# cRamageddon.net
KiCad netlist of a schematic drawn in EasyEDA
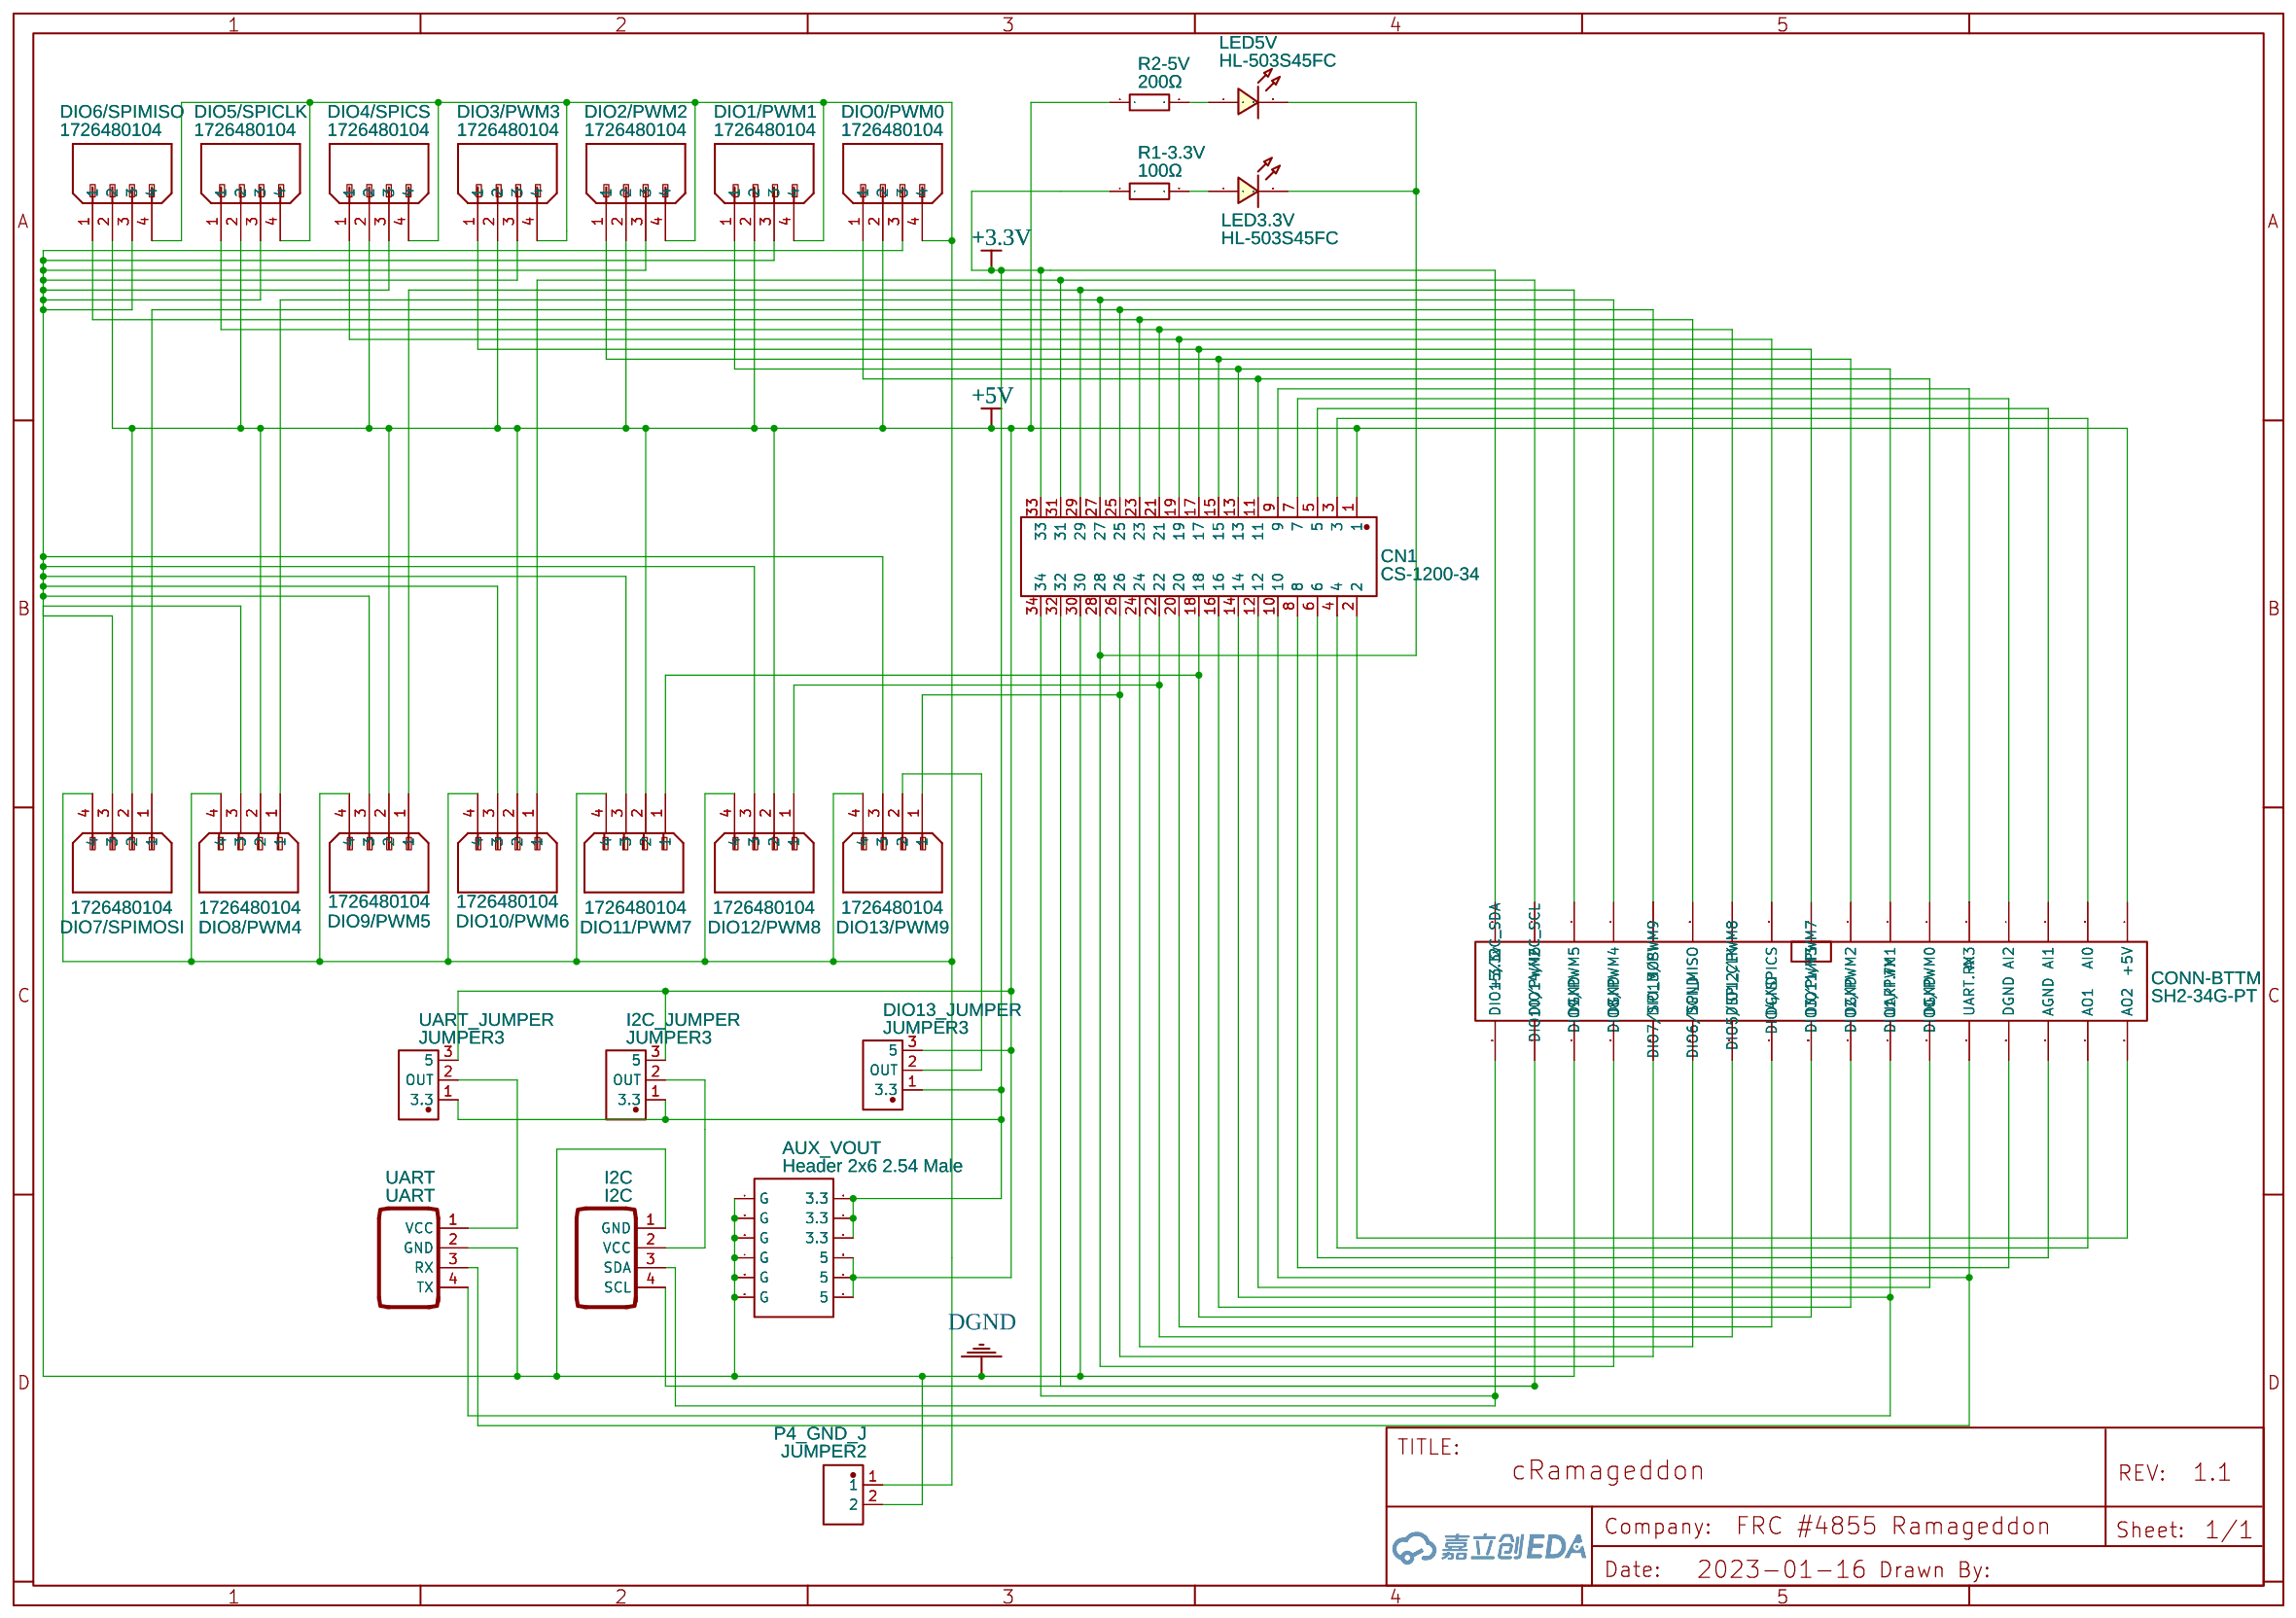
[diagram p0: schematic sheet]

(export (version "E")
  (design (tool "Eeschema 10.0.6"))
  (components
    (comp (ref "AUX_VOUT")
      (value "Header 2x6 2.54 Male")
      (fields (field (name "BOM_Supplier Part") "2X5/2.54"))
      (libsource (lib "") (part "Header 2x6 2.54 Male"))
    )
    (comp (ref "CN1")
      (value "CS-1200-34")
      (fields (field (name "BOM_Supplier Part") "C2886707"))
      (libsource (lib "") (part "CS-1200-34"))
    )
    (comp (ref "CONN-BTTM") (value "SH2-34G-PT") (libsource (lib "") (part "SH2-34G-PT")))
    (comp (ref "DIO0/PWM0") (value "1726480104") (libsource (lib "") (part "1726480104_1")))
    (comp (ref "DIO1/PWM1") (value "1726480104") (libsource (lib "") (part "1726480104_13")))
    (comp (ref "DIO2/PWM2") (value "1726480104") (libsource (lib "") (part "1726480104_7")))
    (comp (ref "DIO3/PWM3") (value "1726480104") (libsource (lib "") (part "1726480104_12")))
    (comp (ref "DIO4/SPICS") (value "1726480104") (libsource (lib "") (part "1726480104_4")))
    (comp (ref "DIO5/SPICLK") (value "1726480104") (libsource (lib "") (part "1726480104_8")))
    (comp (ref "DIO6/SPIMISO") (value "1726480104") (libsource (lib "") (part "1726480104_3")))
    (comp (ref "DIO7/SPIMOSI") (value "1726480104") (libsource (lib "") (part "1726480104")))
    (comp (ref "DIO8/PWM4") (value "1726480104") (libsource (lib "") (part "1726480104_11")))
    (comp (ref "DIO9/PWM5") (value "1726480104") (libsource (lib "") (part "1726480104_9")))
    (comp (ref "DIO10/PWM6") (value "1726480104") (libsource (lib "") (part "1726480104_6")))
    (comp (ref "DIO11/PWM7") (value "1726480104") (libsource (lib "") (part "1726480104_2")))
    (comp (ref "DIO12/PWM8") (value "1726480104") (libsource (lib "") (part "1726480104_10")))
    (comp (ref "DIO13/PWM9") (value "1726480104") (libsource (lib "") (part "1726480104_5")))
    (comp (ref "DIO13_JUMPER")
      (value "JUMPER3")
      (fields (field (name "BOM_Manufacturer Part") "Jumper3") (field (name "BOM_Supplier Part") "C2940050"))
      (libsource (lib "") (part "JUMPER3_1"))
    )
    (comp (ref "I2C")
      (value "I2C")
      (fields (field (name "BOM_Supplier Part") "Módulo para LCD"))
      (libsource (lib "") (part "I2C_1"))
    )
    (comp (ref "I2C_JUMPER")
      (value "JUMPER3")
      (fields (field (name "BOM_Manufacturer Part") "Jumper3") (field (name "BOM_Supplier Part") "C2940050"))
      (libsource (lib "") (part "JUMPER3_2"))
    )
    (comp (ref "LED3.3V")
      (value "HL-503S45FC")
      (fields (field (name "BOM_Supplier Part") "C568942"))
      (libsource (lib "") (part "HL-503S45FC"))
    )
    (comp (ref "LED5V")
      (value "HL-503S45FC")
      (fields (field (name "BOM_Supplier Part") "C568942"))
      (libsource (lib "") (part "HL-503S45FC_1"))
    )
    (comp (ref "P4_GND_J")
      (value "JUMPER2")
      (fields (field (name "BOM_Manufacturer Part") "Jumper2") (field (name "BOM_Supplier Part") "C2940092"))
      (libsource (lib "") (part "JUMPER2"))
    )
    (comp (ref "R1-3.3V")
      (value "100Ω")
      (fields
        (field (name "BOM_Manufacturer Part") "MFR0W4F1800A50")
        (field (name "BOM_Supplier Part") "C58665")
      )
      (libsource (lib "") (part "MFR0W4F1800A50_1"))
    )
    (comp (ref "R2-5V")
      (value "200Ω")
      (fields
        (field (name "BOM_Manufacturer Part") "MFR0W4F1800A50")
        (field (name "BOM_Supplier Part") "C58665")
      )
      (libsource (lib "") (part "MFR0W4F1800A50"))
    )
    (comp (ref "UART")
      (value "UART")
      (fields (field (name "BOM_Supplier Part") "Módulo para LCD"))
      (libsource (lib "") (part "I2C"))
    )
    (comp (ref "UART_JUMPER")
      (value "JUMPER3")
      (fields (field (name "BOM_Manufacturer Part") "Jumper3") (field (name "BOM_Supplier Part") "C2940050"))
      (libsource (lib "") (part "JUMPER3"))
    )
  )
  (nets
    (net (code "1") (name "+3.3V") (class "Default")
      (node (ref "AUX_VOUT") (pin "2") (pinfunction "3.3_2") (pintype "unspecified"))
      (node (ref "AUX_VOUT") (pin "4") (pinfunction "3.3_4") (pintype "unspecified"))
      (node (ref "AUX_VOUT") (pin "6") (pinfunction "3.3_6") (pintype "unspecified"))
      (node (ref "CN1") (pin "33") (pinfunction "33_33") (pintype "unspecified"))
      (node (ref "CONN-BTTM") (pin "33") (pinfunction "+3.3v_33") (pintype "unspecified"))
      (node (ref "DIO13_JUMPER") (pin "1") (pinfunction "3.3_1") (pintype "unspecified"))
      (node (ref "I2C_JUMPER") (pin "1") (pinfunction "3.3_1") (pintype "unspecified"))
      (node (ref "R1-3.3V") (pin "1") (pinfunction "1_1") (pintype "input"))
      (node (ref "UART_JUMPER") (pin "1") (pinfunction "3.3_1") (pintype "unspecified"))
    )
    (net (code "2") (name "+5V") (class "Default")
      (node (ref "AUX_VOUT") (pin "10") (pinfunction "5_10") (pintype "unspecified"))
      (node (ref "AUX_VOUT") (pin "12") (pinfunction "5_12") (pintype "unspecified"))
      (node (ref "AUX_VOUT") (pin "8") (pinfunction "5_8") (pintype "unspecified"))
      (node (ref "CN1") (pin "1") (pinfunction "1_1") (pintype "unspecified"))
      (node (ref "CONN-BTTM") (pin "1") (pinfunction "+5V_1") (pintype "unspecified"))
      (node (ref "DIO0/PWM0") (pin "2") (pinfunction "2_2") (pintype "bidirectional"))
      (node (ref "DIO1/PWM1") (pin "2") (pinfunction "2_2") (pintype "bidirectional"))
      (node (ref "DIO10/PWM6") (pin "2") (pinfunction "2_2") (pintype "bidirectional"))
      (node (ref "DIO11/PWM7") (pin "2") (pinfunction "2_2") (pintype "bidirectional"))
      (node (ref "DIO12/PWM8") (pin "2") (pinfunction "2_2") (pintype "bidirectional"))
      (node (ref "DIO13_JUMPER") (pin "3") (pinfunction "5_3") (pintype "unspecified"))
      (node (ref "DIO2/PWM2") (pin "2") (pinfunction "2_2") (pintype "bidirectional"))
      (node (ref "DIO3/PWM3") (pin "2") (pinfunction "2_2") (pintype "bidirectional"))
      (node (ref "DIO4/SPICS") (pin "2") (pinfunction "2_2") (pintype "bidirectional"))
      (node (ref "DIO5/SPICLK") (pin "2") (pinfunction "2_2") (pintype "bidirectional"))
      (node (ref "DIO6/SPIMISO") (pin "2") (pinfunction "2_2") (pintype "bidirectional"))
      (node (ref "DIO7/SPIMOSI") (pin "2") (pinfunction "2_2") (pintype "bidirectional"))
      (node (ref "DIO8/PWM4") (pin "2") (pinfunction "2_2") (pintype "bidirectional"))
      (node (ref "DIO9/PWM5") (pin "2") (pinfunction "2_2") (pintype "bidirectional"))
      (node (ref "I2C_JUMPER") (pin "3") (pinfunction "5_3") (pintype "unspecified"))
      (node (ref "R2-5V") (pin "1") (pinfunction "1_1") (pintype "input"))
      (node (ref "UART_JUMPER") (pin "3") (pinfunction "5_3") (pintype "unspecified"))
    )
    (net (code "3") (name "DGND") (class "Default")
      (node (ref "AUX_VOUT") (pin "1") (pinfunction "G_1") (pintype "unspecified"))
      (node (ref "AUX_VOUT") (pin "11") (pinfunction "G_11") (pintype "unspecified"))
      (node (ref "AUX_VOUT") (pin "3") (pinfunction "G_3") (pintype "unspecified"))
      (node (ref "AUX_VOUT") (pin "5") (pinfunction "G_5") (pintype "unspecified"))
      (node (ref "AUX_VOUT") (pin "7") (pinfunction "G_7") (pintype "unspecified"))
      (node (ref "AUX_VOUT") (pin "9") (pinfunction "G_9") (pintype "unspecified"))
      (node (ref "CN1") (pin "30") (pinfunction "30_30") (pintype "unspecified"))
      (node (ref "CONN-BTTM") (pin "30") (pinfunction "DGND_30") (pintype "unspecified"))
      (node (ref "DIO0/PWM0") (pin "3") (pinfunction "3_3") (pintype "bidirectional"))
      (node (ref "DIO1/PWM1") (pin "3") (pinfunction "3_3") (pintype "bidirectional"))
      (node (ref "DIO10/PWM6") (pin "3") (pinfunction "3_3") (pintype "bidirectional"))
      (node (ref "DIO11/PWM7") (pin "3") (pinfunction "3_3") (pintype "bidirectional"))
      (node (ref "DIO12/PWM8") (pin "3") (pinfunction "3_3") (pintype "bidirectional"))
      (node (ref "DIO13/PWM9") (pin "3") (pinfunction "3_3") (pintype "bidirectional"))
      (node (ref "DIO2/PWM2") (pin "3") (pinfunction "3_3") (pintype "bidirectional"))
      (node (ref "DIO3/PWM3") (pin "3") (pinfunction "3_3") (pintype "bidirectional"))
      (node (ref "DIO4/SPICS") (pin "3") (pinfunction "3_3") (pintype "bidirectional"))
      (node (ref "DIO5/SPICLK") (pin "3") (pinfunction "3_3") (pintype "bidirectional"))
      (node (ref "DIO6/SPIMISO") (pin "3") (pinfunction "3_3") (pintype "bidirectional"))
      (node (ref "DIO9/PWM5") (pin "3") (pinfunction "3_3") (pintype "bidirectional"))
      (node (ref "I2C") (pin "1") (pinfunction "GND_1") (pintype "unspecified"))
      (node (ref "P4_GND_J") (pin "2") (pinfunction "2_2") (pintype "unspecified"))
      (node (ref "UART") (pin "2") (pinfunction "GND_2") (pintype "unspecified"))
    )
    (net (code "4") (name "Net-(CN1-Pad8)") (class "Default")
      (node (ref "CN1") (pin "8") (pinfunction "8_8") (pintype "unspecified"))
      (node (ref "CONN-BTTM") (pin "8") (pinfunction "DGND_8") (pintype "unspecified"))
    )
    (net (code "5") (name "Net-(CN1-Pad12)") (class "Default")
      (node (ref "CN1") (pin "12") (pinfunction "12_12") (pintype "unspecified"))
      (node (ref "CONN-BTTM") (pin "12") (pinfunction "DGND_12") (pintype "unspecified"))
    )
    (net (code "6") (name "Net-(CN1-Pad16)") (class "Default")
      (node (ref "CN1") (pin "16") (pinfunction "16_16") (pintype "unspecified"))
      (node (ref "CONN-BTTM") (pin "16") (pinfunction "DGND_16") (pintype "unspecified"))
    )
    (net (code "7") (name "Net-(CN1-Pad20)") (class "Default")
      (node (ref "CN1") (pin "20") (pinfunction "20_20") (pintype "unspecified"))
      (node (ref "CONN-BTTM") (pin "20") (pinfunction "DGND_20") (pintype "unspecified"))
    )
    (net (code "8") (name "Net-(CN1-Pad24)") (class "Default")
      (node (ref "CN1") (pin "24") (pinfunction "24_24") (pintype "unspecified"))
      (node (ref "CONN-BTTM") (pin "24") (pinfunction "DGND_24") (pintype "unspecified"))
    )
    (net (code "9") (name "Net-(CN1-Pad28)") (class "Default")
      (node (ref "CN1") (pin "28") (pinfunction "28_28") (pintype "unspecified"))
      (node (ref "CONN-BTTM") (pin "28") (pinfunction "DGND_28") (pintype "unspecified"))
      (node (ref "LED3.3V") (pin "2") (pinfunction "2_2") (pintype "unspecified"))
      (node (ref "LED5V") (pin "2") (pinfunction "2_2") (pintype "unspecified"))
    )
    (net (code "10") (name "Net-(CONN-BTTM-AGND)") (class "Default")
      (node (ref "CN1") (pin "6") (pinfunction "6_6") (pintype "unspecified"))
      (node (ref "CONN-BTTM") (pin "6") (pinfunction "AGND_6") (pintype "unspecified"))
    )
    (net (code "11") (name "Net-(CONN-BTTM-AI0)") (class "Default")
      (node (ref "CN1") (pin "3") (pinfunction "3_3") (pintype "unspecified"))
      (node (ref "CONN-BTTM") (pin "3") (pinfunction "AI0_3") (pintype "unspecified"))
    )
    (net (code "12") (name "Net-(CONN-BTTM-AI1)") (class "Default")
      (node (ref "CN1") (pin "5") (pinfunction "5_5") (pintype "unspecified"))
      (node (ref "CONN-BTTM") (pin "5") (pinfunction "AI1_5") (pintype "unspecified"))
    )
    (net (code "13") (name "Net-(CONN-BTTM-AI2)") (class "Default")
      (node (ref "CN1") (pin "7") (pinfunction "7_7") (pintype "unspecified"))
      (node (ref "CONN-BTTM") (pin "7") (pinfunction "AI2_7") (pintype "unspecified"))
    )
    (net (code "14") (name "Net-(CONN-BTTM-AI3)") (class "Default")
      (node (ref "CN1") (pin "9") (pinfunction "9_9") (pintype "unspecified"))
      (node (ref "CONN-BTTM") (pin "9") (pinfunction "AI3_9") (pintype "unspecified"))
    )
    (net (code "15") (name "Net-(CONN-BTTM-AO1)") (class "Default")
      (node (ref "CN1") (pin "4") (pinfunction "4_4") (pintype "unspecified"))
      (node (ref "CONN-BTTM") (pin "4") (pinfunction "AO1_4") (pintype "unspecified"))
    )
    (net (code "16") (name "Net-(CONN-BTTM-AO2)") (class "Default")
      (node (ref "CN1") (pin "2") (pinfunction "2_2") (pintype "unspecified"))
      (node (ref "CONN-BTTM") (pin "2") (pinfunction "AO2_2") (pintype "unspecified"))
    )
    (net (code "17") (name "Net-(CONN-BTTM-DIO0{slash}PWM0)") (class "Default")
      (node (ref "CN1") (pin "11") (pinfunction "11_11") (pintype "unspecified"))
      (node (ref "CONN-BTTM") (pin "11") (pinfunction "DIO0/PWM0_11") (pintype "unspecified"))
      (node (ref "DIO0/PWM0") (pin "1") (pinfunction "1_1") (pintype "bidirectional"))
    )
    (net (code "18") (name "Net-(CONN-BTTM-DIO1{slash}PWM1)") (class "Default")
      (node (ref "CN1") (pin "13") (pinfunction "13_13") (pintype "unspecified"))
      (node (ref "CONN-BTTM") (pin "13") (pinfunction "DIO1/PWM1_13") (pintype "unspecified"))
      (node (ref "DIO1/PWM1") (pin "1") (pinfunction "1_1") (pintype "bidirectional"))
    )
    (net (code "19") (name "Net-(CONN-BTTM-DIO2{slash}PWM2)") (class "Default")
      (node (ref "CN1") (pin "15") (pinfunction "15_15") (pintype "unspecified"))
      (node (ref "CONN-BTTM") (pin "15") (pinfunction "DIO2/PWM2_15") (pintype "unspecified"))
      (node (ref "DIO2/PWM2") (pin "1") (pinfunction "1_1") (pintype "bidirectional"))
    )
    (net (code "20") (name "Net-(CONN-BTTM-DIO3{slash}PWM3)") (class "Default")
      (node (ref "CN1") (pin "17") (pinfunction "17_17") (pintype "unspecified"))
      (node (ref "CONN-BTTM") (pin "17") (pinfunction "DIO3/PWM3_17") (pintype "unspecified"))
      (node (ref "DIO3/PWM3") (pin "1") (pinfunction "1_1") (pintype "bidirectional"))
    )
    (net (code "21") (name "Net-(CONN-BTTM-DIO4{slash}SPICS)") (class "Default")
      (node (ref "CN1") (pin "19") (pinfunction "19_19") (pintype "unspecified"))
      (node (ref "CONN-BTTM") (pin "19") (pinfunction "DIO4/SPICS_19") (pintype "unspecified"))
      (node (ref "DIO4/SPICS") (pin "1") (pinfunction "1_1") (pintype "bidirectional"))
    )
    (net (code "22") (name "Net-(CONN-BTTM-DIO5{slash}SPI_CLK)") (class "Default")
      (node (ref "CN1") (pin "21") (pinfunction "21_21") (pintype "unspecified"))
      (node (ref "CONN-BTTM") (pin "21") (pinfunction "DIO5/SPI_CLK_21") (pintype "unspecified"))
      (node (ref "DIO5/SPICLK") (pin "1") (pinfunction "1_1") (pintype "bidirectional"))
    )
    (net (code "23") (name "Net-(CONN-BTTM-DIO6{slash}SPI_MISO)") (class "Default")
      (node (ref "CN1") (pin "23") (pinfunction "23_23") (pintype "unspecified"))
      (node (ref "CONN-BTTM") (pin "23") (pinfunction "DIO6/SPI_MISO_23") (pintype "unspecified"))
      (node (ref "DIO6/SPIMISO") (pin "1") (pinfunction "1_1") (pintype "bidirectional"))
    )
    (net (code "24") (name "Net-(CONN-BTTM-DIO7{slash}SPI_MOSI)") (class "Default")
      (node (ref "CN1") (pin "25") (pinfunction "25_25") (pintype "unspecified"))
      (node (ref "CONN-BTTM") (pin "25") (pinfunction "DIO7/SPI_MOSI_25") (pintype "unspecified"))
      (node (ref "DIO7/SPIMOSI") (pin "1") (pinfunction "1_1") (pintype "bidirectional"))
    )
    (net (code "25") (name "Net-(CONN-BTTM-DIO8{slash}PWM4)") (class "Default")
      (node (ref "CN1") (pin "27") (pinfunction "27_27") (pintype "unspecified"))
      (node (ref "CONN-BTTM") (pin "27") (pinfunction "DIO8/PWM4_27") (pintype "unspecified"))
      (node (ref "DIO8/PWM4") (pin "1") (pinfunction "1_1") (pintype "bidirectional"))
    )
    (net (code "26") (name "Net-(CONN-BTTM-DIO9{slash}PWM5)") (class "Default")
      (node (ref "CN1") (pin "29") (pinfunction "29_29") (pintype "unspecified"))
      (node (ref "CONN-BTTM") (pin "29") (pinfunction "DIO9/PWM5_29") (pintype "unspecified"))
      (node (ref "DIO9/PWM5") (pin "1") (pinfunction "1_1") (pintype "bidirectional"))
    )
    (net (code "27") (name "Net-(CONN-BTTM-DIO10{slash}PWM6)") (class "Default")
      (node (ref "CN1") (pin "31") (pinfunction "31_31") (pintype "unspecified"))
      (node (ref "CONN-BTTM") (pin "31") (pinfunction "DIO10/PWM6_31") (pintype "unspecified"))
      (node (ref "DIO10/PWM6") (pin "1") (pinfunction "1_1") (pintype "bidirectional"))
    )
    (net (code "28") (name "Net-(CONN-BTTM-DIO11{slash}PWM7)") (class "Default")
      (node (ref "CN1") (pin "18") (pinfunction "18_18") (pintype "unspecified"))
      (node (ref "CONN-BTTM") (pin "18") (pinfunction "DIO11/PWM7_18") (pintype "unspecified"))
      (node (ref "DIO11/PWM7") (pin "1") (pinfunction "1_1") (pintype "bidirectional"))
    )
    (net (code "29") (name "Net-(CONN-BTTM-DIO12{slash}PWM8)") (class "Default")
      (node (ref "CN1") (pin "22") (pinfunction "22_22") (pintype "unspecified"))
      (node (ref "CONN-BTTM") (pin "22") (pinfunction "DIO12/PWM8_22") (pintype "unspecified"))
      (node (ref "DIO12/PWM8") (pin "1") (pinfunction "1_1") (pintype "bidirectional"))
    )
    (net (code "30") (name "Net-(CONN-BTTM-DIO13{slash}PWM9)") (class "Default")
      (node (ref "CN1") (pin "26") (pinfunction "26_26") (pintype "unspecified"))
      (node (ref "CONN-BTTM") (pin "26") (pinfunction "DIO13/PWM9_26") (pintype "unspecified"))
      (node (ref "DIO13/PWM9") (pin "1") (pinfunction "1_1") (pintype "bidirectional"))
    )
    (net (code "31") (name "Net-(CONN-BTTM-DIO14{slash}I2C_SCL)") (class "Default")
      (node (ref "CN1") (pin "32") (pinfunction "32_32") (pintype "unspecified"))
      (node (ref "CONN-BTTM") (pin "32") (pinfunction "DIO14/I2C_SCL_32") (pintype "unspecified"))
      (node (ref "I2C") (pin "4") (pinfunction "SCL_4") (pintype "unspecified"))
    )
    (net (code "32") (name "Net-(CONN-BTTM-DIO15{slash}I2C_SDA)") (class "Default")
      (node (ref "CN1") (pin "34") (pinfunction "34_34") (pintype "unspecified"))
      (node (ref "CONN-BTTM") (pin "34") (pinfunction "DIO15/I2C_SDA_34") (pintype "unspecified"))
      (node (ref "I2C") (pin "3") (pinfunction "SDA_3") (pintype "unspecified"))
    )
    (net (code "33") (name "Net-(CONN-BTTM-UART.RX)") (class "Default")
      (node (ref "CN1") (pin "10") (pinfunction "10_10") (pintype "unspecified"))
      (node (ref "CONN-BTTM") (pin "10") (pinfunction "UART.RX_10") (pintype "unspecified"))
      (node (ref "UART") (pin "3") (pinfunction "RX_3") (pintype "unspecified"))
    )
    (net (code "34") (name "Net-(CONN-BTTM-UART.TX)") (class "Default")
      (node (ref "CN1") (pin "14") (pinfunction "14_14") (pintype "unspecified"))
      (node (ref "CONN-BTTM") (pin "14") (pinfunction "UART.TX_14") (pintype "unspecified"))
      (node (ref "UART") (pin "4") (pinfunction "TX_4") (pintype "unspecified"))
    )
    (net (code "35") (name "Net-(DIO0/PWM0-Pad4)") (class "Default")
      (node (ref "DIO0/PWM0") (pin "4") (pinfunction "4_4") (pintype "bidirectional"))
      (node (ref "DIO1/PWM1") (pin "4") (pinfunction "4_4") (pintype "bidirectional"))
      (node (ref "DIO10/PWM6") (pin "4") (pinfunction "4_4") (pintype "bidirectional"))
      (node (ref "DIO11/PWM7") (pin "4") (pinfunction "4_4") (pintype "bidirectional"))
      (node (ref "DIO12/PWM8") (pin "4") (pinfunction "4_4") (pintype "bidirectional"))
      (node (ref "DIO13/PWM9") (pin "4") (pinfunction "4_4") (pintype "bidirectional"))
      (node (ref "DIO2/PWM2") (pin "4") (pinfunction "4_4") (pintype "bidirectional"))
      (node (ref "DIO3/PWM3") (pin "4") (pinfunction "4_4") (pintype "bidirectional"))
      (node (ref "DIO4/SPICS") (pin "4") (pinfunction "4_4") (pintype "bidirectional"))
      (node (ref "DIO5/SPICLK") (pin "4") (pinfunction "4_4") (pintype "bidirectional"))
      (node (ref "DIO6/SPIMISO") (pin "4") (pinfunction "4_4") (pintype "bidirectional"))
      (node (ref "DIO7/SPIMOSI") (pin "4") (pinfunction "4_4") (pintype "bidirectional"))
      (node (ref "DIO8/PWM4") (pin "4") (pinfunction "4_4") (pintype "bidirectional"))
      (node (ref "DIO9/PWM5") (pin "4") (pinfunction "4_4") (pintype "bidirectional"))
      (node (ref "P4_GND_J") (pin "1") (pinfunction "1_1") (pintype "unspecified"))
    )
    (net (code "36") (name "Net-(DIO7/SPIMOSI-Pad3)") (class "Default")
      (node (ref "DIO7/SPIMOSI") (pin "3") (pinfunction "3_3") (pintype "bidirectional"))
      (node (ref "DIO8/PWM4") (pin "3") (pinfunction "3_3") (pintype "bidirectional"))
    )
    (net (code "37") (name "Net-(DIO13_JUMPER-OUT)") (class "Default")
      (node (ref "DIO13/PWM9") (pin "2") (pinfunction "2_2") (pintype "bidirectional"))
      (node (ref "DIO13_JUMPER") (pin "2") (pinfunction "OUT_2") (pintype "unspecified"))
    )
    (net (code "38") (name "Net-(I2C-VCC)") (class "Default")
      (node (ref "I2C") (pin "2") (pinfunction "VCC_2") (pintype "unspecified"))
      (node (ref "I2C_JUMPER") (pin "2") (pinfunction "OUT_2") (pintype "unspecified"))
    )
    (net (code "39") (name "Net-(LED3.3V-Pad1)") (class "Default")
      (node (ref "LED3.3V") (pin "1") (pinfunction "1_1") (pintype "unspecified"))
      (node (ref "R1-3.3V") (pin "2") (pinfunction "2_2") (pintype "input"))
    )
    (net (code "40") (name "Net-(LED5V-Pad1)") (class "Default")
      (node (ref "LED5V") (pin "1") (pinfunction "1_1") (pintype "unspecified"))
      (node (ref "R2-5V") (pin "2") (pinfunction "2_2") (pintype "input"))
    )
    (net (code "41") (name "Net-(UART-VCC)") (class "Default")
      (node (ref "UART") (pin "1") (pinfunction "VCC_1") (pintype "unspecified"))
      (node (ref "UART_JUMPER") (pin "2") (pinfunction "OUT_2") (pintype "unspecified"))
    )
  )
)
